# RFM12BS.net
KiCad netlist of a schematic drawn in Altium Designer
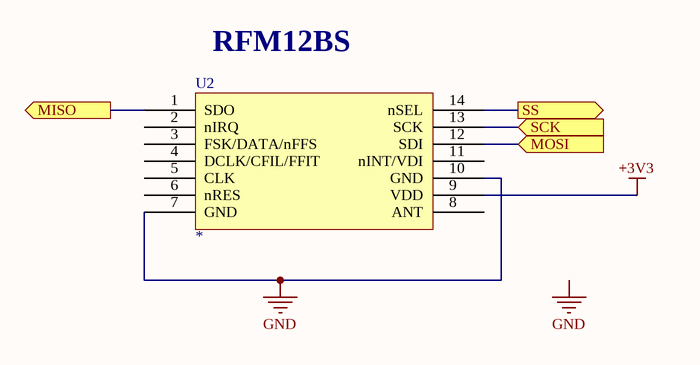
[diagram p0: RFM12BS.SchDoc]

(export (version "E")
  (design (tool "Eeschema 10.0.6"))
  (components (comp (ref "U2") (value "*") (libsource (lib "Parts") (part "RFM12BS"))))
  (nets
    (net (code "1") (name "+3V3") (class "Default")
      (node (ref "U2") (pin "9") (pinfunction "VDD_9") (pintype "passive"))
    )
    (net (code "2") (name "/MISO") (class "Default")
      (node (ref "U2") (pin "1") (pinfunction "SDO_1") (pintype "passive"))
    )
    (net (code "3") (name "/MOSI") (class "Default")
      (node (ref "U2") (pin "12") (pinfunction "SDI_12") (pintype "passive"))
    )
    (net (code "4") (name "/SCK") (class "Default")
      (node (ref "U2") (pin "13") (pinfunction "SCK_13") (pintype "passive"))
    )
    (net (code "5") (name "/SS") (class "Default")
      (node (ref "U2") (pin "14") (pinfunction "nSEL_14") (pintype "passive"))
    )
    (net (code "6") (name "GND") (class "Default")
      (node (ref "U2") (pin "10") (pinfunction "GND_10") (pintype "passive"))
      (node (ref "U2") (pin "7") (pinfunction "GND_7") (pintype "passive"))
    )
    (net (code "7") (name "unconnected-(U2-ANT-Pad8)") (class "Default")
      (node (ref "U2") (pin "8") (pinfunction "ANT_8") (pintype "passive"))
    )
    (net (code "8") (name "unconnected-(U2-CLK-Pad5)") (class "Default")
      (node (ref "U2") (pin "5") (pinfunction "CLK_5") (pintype "passive"))
    )
    (net (code "9") (name "unconnected-(U2-DCLK{slash}CFIL{slash}FFIT-Pad4)") (class "Default")
      (node (ref "U2") (pin "4") (pinfunction "DCLK/CFIL/FFIT_4") (pintype "passive"))
    )
    (net (code "10") (name "unconnected-(U2-FSK{slash}DATA{slash}nFFS-Pad3)") (class "Default")
      (node (ref "U2") (pin "3") (pinfunction "FSK/DATA/nFFS_3") (pintype "passive"))
    )
    (net (code "11") (name "unconnected-(U2-nINT{slash}VDI-Pad11)") (class "Default")
      (node (ref "U2") (pin "11") (pinfunction "nINT/VDI_11") (pintype "passive"))
    )
    (net (code "12") (name "unconnected-(U2-nIRQ-Pad2)") (class "Default")
      (node (ref "U2") (pin "2") (pinfunction "nIRQ_2") (pintype "passive"))
    )
    (net (code "13") (name "unconnected-(U2-nRES-Pad6)") (class "Default")
      (node (ref "U2") (pin "6") (pinfunction "nRES_6") (pintype "passive"))
    )
  )
)
